# 780-00057_rev1_Pg1_SCH_NRES_Crate_Slot_M.net
KiCad netlist of a schematic drawn in Altium Designer
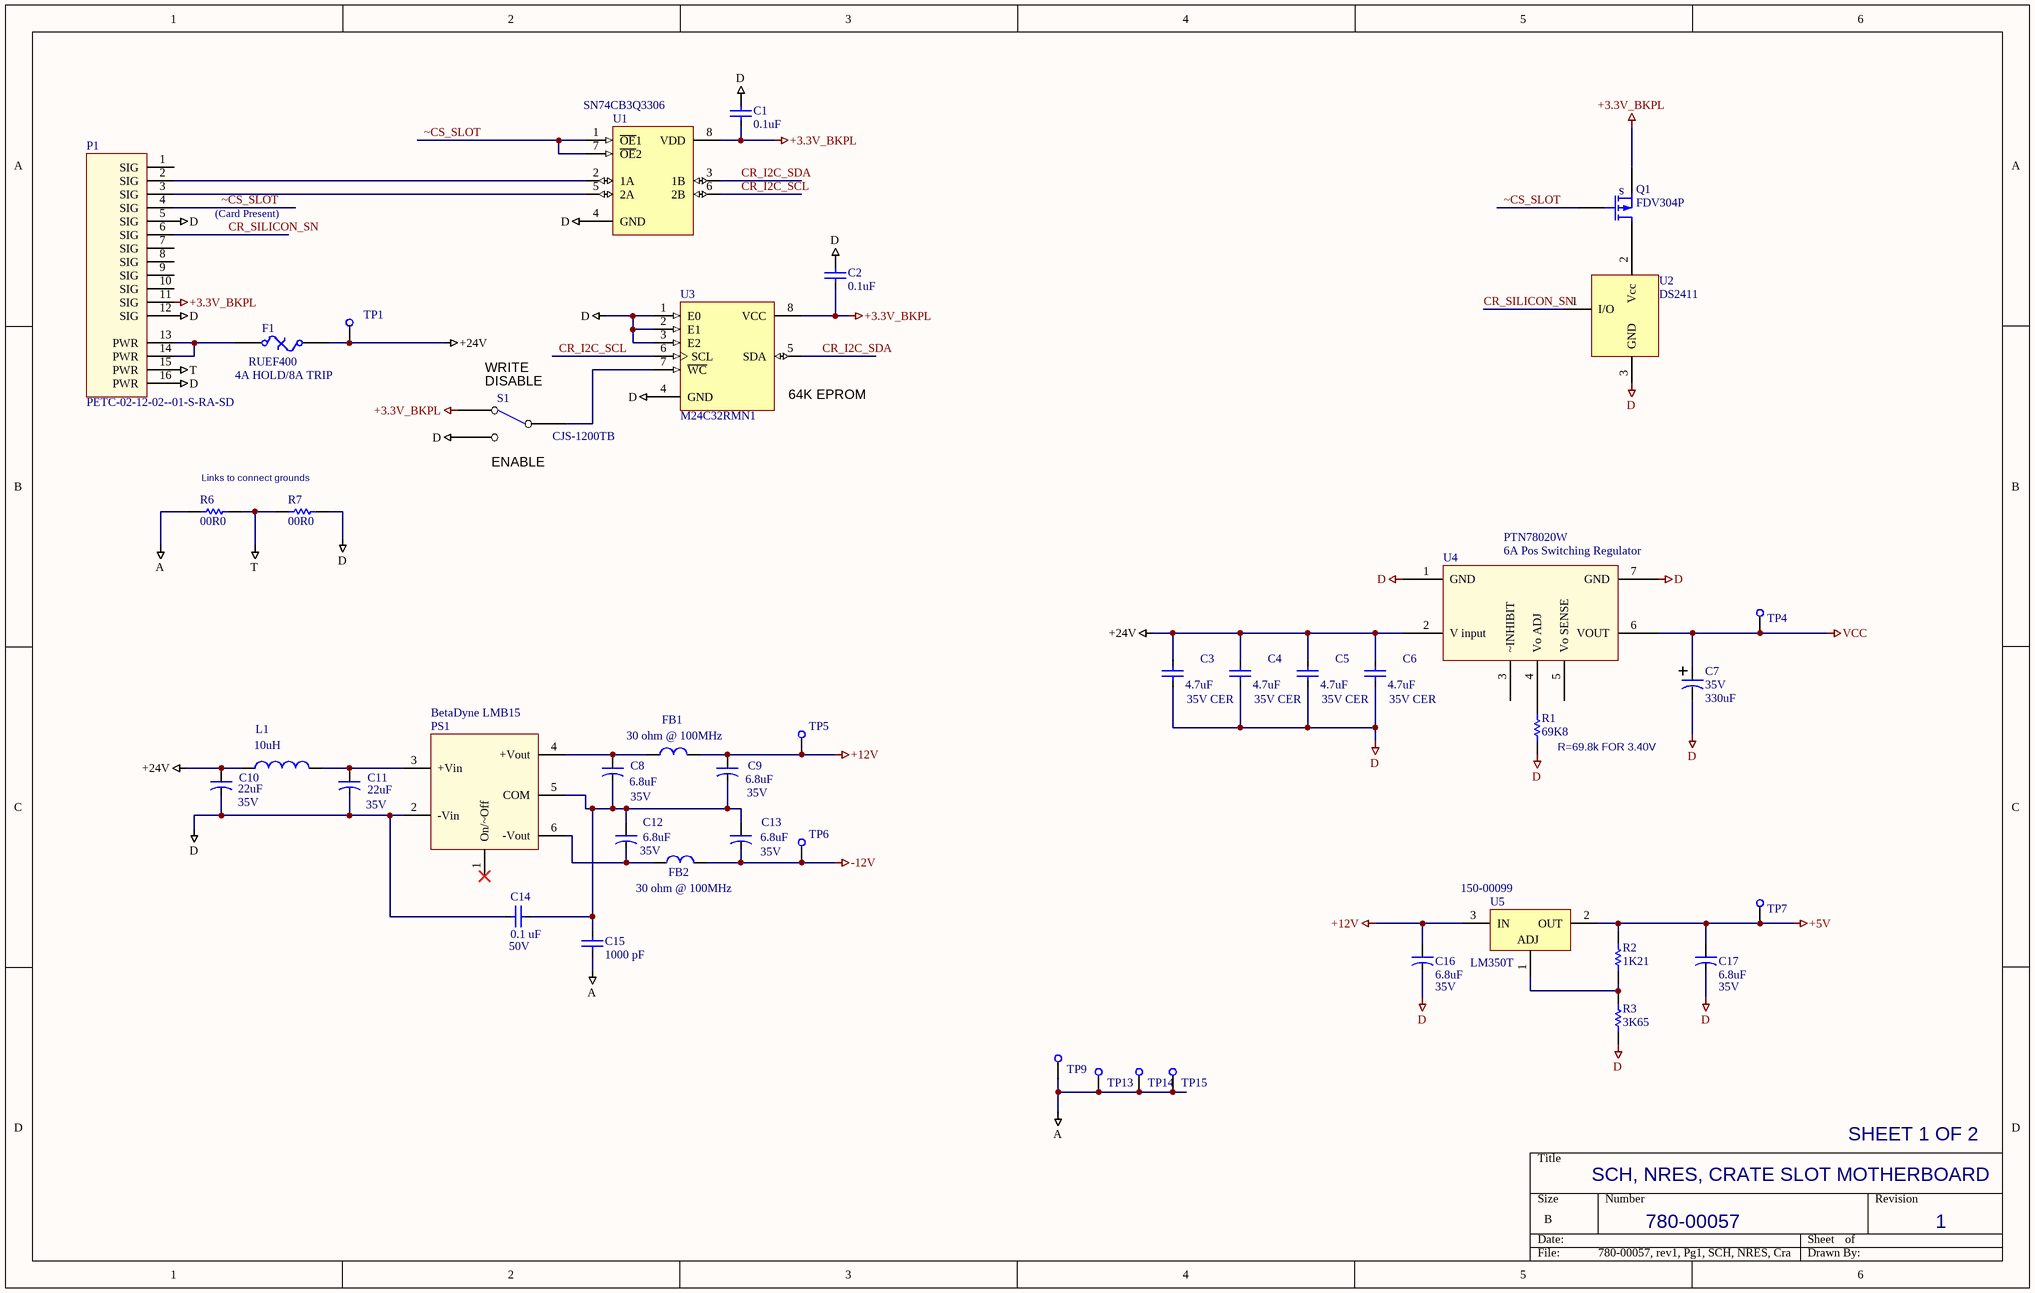
[diagram p0: 780-00057, rev1, Pg1, SCH, NRES, Crate Slot MotherBoard.SchDoc]

(export (version "E")
  (design (tool "Eeschema 10.0.6"))
  (components
    (comp (ref "C1")
      (value "0.1uF")
      (footprint "SMD_0805")
      (description "Capacitor")
      (fields (field (name "MANUFACTURER") "AVX") (field (name "Comment") "Cap SMD"))
      (libsource (lib "Richs Schematic Components") (part "Cap SMD"))
    )
    (comp (ref "C2")
      (value "0.1uF")
      (footprint "SMD_0805")
      (description "Capacitor")
      (fields (field (name "MANUFACTURER") "AVX") (field (name "Comment") "Cap SMD"))
      (libsource (lib "Richs Schematic Components") (part "Cap SMD"))
    )
    (comp (ref "C3")
      (value "35V CER")
      (footprint "SMD_0805")
      (description "Capacitor")
      (fields (field (name "ALTIUM_VALUE") "4.7uF"))
      (libsource (lib "Richs Schematic Components") (part "Cap SMD"))
    )
    (comp (ref "C4")
      (value "35V CER")
      (footprint "SMD_0805")
      (description "Capacitor")
      (fields (field (name "ALTIUM_VALUE") "4.7uF"))
      (libsource (lib "Richs Schematic Components") (part "Cap SMD"))
    )
    (comp (ref "C5")
      (value "35V CER")
      (footprint "SMD_0805")
      (description "Capacitor")
      (fields (field (name "ALTIUM_VALUE") "4.7uF"))
      (libsource (lib "Richs Schematic Components") (part "Cap SMD"))
    )
    (comp (ref "C6")
      (value "35V CER")
      (footprint "SMD_0805")
      (description "Capacitor")
      (fields (field (name "ALTIUM_VALUE") "4.7uF"))
      (libsource (lib "Richs Schematic Components") (part "Cap SMD"))
    )
    (comp (ref "C7")
      (value "35V")
      (footprint "CAP, Thru Hole 10mm dia")
      (description "Radial Thru hole")
      (fields (field (name "ALTIUM_VALUE") "330uF"))
      (libsource (lib "Richs Schematic Components") (part "Cap Elec, 330 uF, 35V"))
    )
    (comp (ref "C8")
      (value "35V")
      (footprint "SMD_CAP_6032")
      (description "outline 6.0mm x 3.2mm")
      (fields (field (name "ALTIUM_VALUE") "6.8uF"))
      (libsource (lib "Richs Schematic Components") (part "Cap Tant 35V"))
    )
    (comp (ref "C9")
      (value "35V")
      (footprint "SMD_CAP_6032")
      (description "outline 6.0mm x 3.2mm")
      (fields (field (name "ALTIUM_VALUE") "6.8uF"))
      (libsource (lib "Richs Schematic Components") (part "Cap Tant 35V"))
    )
    (comp (ref "C10")
      (value "35V")
      (footprint "SMD_CAP_7343")
      (description "outline 6.0mm x 3.2mm")
      (fields (field (name "MANUFACTURER") "Kemet") (field (name "ALTIUM_VALUE") "22uF"))
      (libsource (lib "Richs Schematic Components") (part "Cap Tant 35V"))
    )
    (comp (ref "C11")
      (value "35V")
      (footprint "SMD_CAP_7343")
      (description "outline 6.0mm x 3.2mm")
      (fields (field (name "MANUFACTURER") "Kemet") (field (name "ALTIUM_VALUE") "22uF"))
      (libsource (lib "Richs Schematic Components") (part "Cap Tant 35V"))
    )
    (comp (ref "C12")
      (value "35V")
      (footprint "SMD_CAP_6032")
      (description "outline 6.0mm x 3.2mm")
      (fields (field (name "ALTIUM_VALUE") "6.8uF"))
      (libsource (lib "Richs Schematic Components") (part "Cap Tant 35V"))
    )
    (comp (ref "C13")
      (value "35V")
      (footprint "SMD_CAP_6032")
      (description "outline 6.0mm x 3.2mm")
      (fields (field (name "ALTIUM_VALUE") "6.8uF"))
      (libsource (lib "Richs Schematic Components") (part "Cap Tant 35V"))
    )
    (comp (ref "C14")
      (value "50V")
      (footprint "SMD_0805")
      (description "Capacitor")
      (fields (field (name "ALTIUM_VALUE") "0.1 uF"))
      (libsource (lib "Richs Schematic Components") (part "Cap SMD"))
    )
    (comp (ref "C15")
      (value "1000 pF")
      (footprint "SMD_0805")
      (description "Capacitor")
      (fields (field (name "Comment") "Cap SMD"))
      (libsource (lib "Richs Schematic Components") (part "Cap SMD"))
    )
    (comp (ref "C16")
      (value "35V")
      (footprint "SMD_CAP_6032")
      (description "outline 6.0mm x 3.2mm")
      (fields (field (name "ALTIUM_VALUE") "6.8uF") (field (name "MANUFACTURER") "NICHICON"))
      (libsource (lib "Richs Schematic Components") (part "Cap Tant 35V"))
    )
    (comp (ref "C17")
      (value "35V")
      (footprint "SMD_CAP_6032")
      (description "outline 6.0mm x 3.2mm")
      (fields (field (name "ALTIUM_VALUE") "6.8uF") (field (name "MANUFACTURER") "NICHICON"))
      (libsource (lib "Richs Schematic Components") (part "Cap Tant 35V"))
    )
    (comp (ref "F1")
      (value "RUEF400")
      (footprint "PolySwitch Radial 0.2")
      (description "PolySwitch RUE Series")
      (fields
        (field (name "MANUFACTURER") "Tyco Electronics")
        (field (name "ALTIUM_VALUE") "4A HOLD/8A TRIP")
      )
      (libsource (lib "Richs Schematic Components") (part "Fuse Thermal"))
    )
    (comp (ref "FB1")
      (value "30 ohm @ 100MHz")
      (footprint "SMD_1210_INDUCT")
      (description "Ferrite Bead  SMD 1210")
      (fields (field (name "MANUFACTURER") "Wurth") (field (name "Comment") "Bead"))
      (libsource (lib "Richs Schematic Components") (part "Ferrite Bead SMD 1210"))
    )
    (comp (ref "FB2")
      (value "30 ohm @ 100MHz")
      (footprint "SMD_1210_INDUCT")
      (description "Ferrite Bead  SMD 1210")
      (fields (field (name "MANUFACTURER") "Wurth") (field (name "Comment") "Bead"))
      (libsource (lib "Richs Schematic Components") (part "Ferrite Bead SMD 1210"))
    )
    (comp (ref "L1")
      (value "10uH")
      (footprint "Inductor TDC SLF")
      (description "Inductor")
      (fields (field (name "MANUFACTURER") "TDK") (field (name "Comment") "445-3869-1-ND"))
      (libsource (lib "Richs Schematic Components") (part "Inductor SMD 10uH 1.8A"))
    )
    (comp (ref "P1")
      (value "PETC-02-12-02--01-S-RA-SD")
      (footprint "PETC-02-12-02-01-RA")
      (description "SAMTEC, SIGNAL(12)+PWR(4)")
      (fields (field (name "MANUFACTURER") "SAMTEC"))
      (libsource (lib "Richs Schematic Components") (part "PETC-02-12-02--01-S-RA-SD"))
    )
    (comp (ref "PS1")
      (value "BetaDyne LMB15")
      (footprint "BetaDyne LNB15, DC/DC")
      (description "DC/DC LMB15 15W, Dual Output")
      (libsource (lib "Richs Schematic Components") (part "BetaDyne LMB15"))
    )
    (comp (ref "Q1")
      (value "FDV304P")
      (footprint "SMD_SOT23_3")
      (description "P-MOSFET LOGIC LEVEL")
      (fields (field (name "MANUFACTURER") "Fairchild"))
      (libsource (lib "Richs Schematic Components") (part "FDV304P"))
    )
    (comp (ref "R1")
      (value "69K8")
      (footprint "SMD_0805")
      (description "Resistor 0805")
      (fields (field (name "MANUFACTURER") "Vishay/Dale") (field (name "Comment") "Res 0805"))
      (libsource (lib "Richs Schematic Components") (part "Res SMD"))
    )
    (comp (ref "R2")
      (value "1K21")
      (footprint "SMD_0805")
      (description "Resistor 0805")
      (fields (field (name "MANUFACTURER") "Vishay/Dale") (field (name "Comment") "Res 0805"))
      (libsource (lib "Richs Schematic Components") (part "Res SMD"))
    )
    (comp (ref "R3")
      (value "3K65")
      (footprint "SMD_0805")
      (description "Resistor 0805")
      (fields (field (name "MANUFACTURER") "Vishay/Dale") (field (name "Comment") "Res 0805"))
      (libsource (lib "Richs Schematic Components") (part "Res SMD"))
    )
    (comp (ref "R6")
      (value "00R0")
      (footprint "Protel 99SE BANKS PCB:smd_0805")
      (description "Resistor 0805")
      (fields (field (name "MANUFACTURER") "Vishay/Dale") (field (name "Comment") "Res 0805"))
      (libsource (lib "Richs Schematic Components") (part "Res SMD"))
    )
    (comp (ref "R7")
      (value "00R0")
      (footprint "Protel 99SE BANKS PCB:smd_0805")
      (description "Resistor 0805")
      (fields (field (name "MANUFACTURER") "Vishay/Dale") (field (name "Comment") "Res 0805"))
      (libsource (lib "Richs Schematic Components") (part "Res SMD"))
    )
    (comp (ref "S1")
      (value "CJS-1200TB")
      (footprint "CAS-120B")
      (fields (field (name "MANUFACTURER") "Copal Electronics"))
      (libsource (lib "JON_1_Library") (part "SW_SPDT_DOUG"))
    )
    (comp (ref "TP1")
      (value "Test point")
      (footprint "Protel 99SE BANKS PCB:PAD_80D_052H")
      (description "Test Point")
      (fields (field (name "MANUFACTURER") "Keystone"))
      (libsource (lib "Richs Schematic Components") (part "Test point"))
    )
    (comp (ref "TP4")
      (value "Test point")
      (footprint "Protel 99SE BANKS PCB:PAD_80D_052H")
      (description "Test Point")
      (fields (field (name "MANUFACTURER") "Keystone"))
      (libsource (lib "Richs Schematic Components") (part "Test point"))
    )
    (comp (ref "TP5")
      (value "Test point")
      (footprint "Protel 99SE BANKS PCB:PAD_80D_052H")
      (description "Test Point")
      (fields (field (name "MANUFACTURER") "Keystone"))
      (libsource (lib "Richs Schematic Components") (part "Test point"))
    )
    (comp (ref "TP6")
      (value "Test point")
      (footprint "Protel 99SE BANKS PCB:PAD_80D_052H")
      (description "Test Point")
      (fields (field (name "MANUFACTURER") "Keystone"))
      (libsource (lib "Richs Schematic Components") (part "Test point"))
    )
    (comp (ref "TP7")
      (value "Test point")
      (footprint "Protel 99SE BANKS PCB:PAD_80D_052H")
      (description "Test Point")
      (fields (field (name "MANUFACTURER") "Keystone"))
      (libsource (lib "Richs Schematic Components") (part "Test point"))
    )
    (comp (ref "TP9")
      (value "Test point")
      (footprint "Protel 99SE BANKS PCB:PAD_80D_052H")
      (description "Test Point")
      (fields (field (name "MANUFACTURER") "Keystone"))
      (libsource (lib "Richs Schematic Components") (part "Test point"))
    )
    (comp (ref "TP13")
      (value "Test point")
      (footprint "Protel 99SE BANKS PCB:PAD_80D_052H")
      (description "Test Point")
      (fields (field (name "MANUFACTURER") "Keystone"))
      (libsource (lib "Richs Schematic Components") (part "Test point"))
    )
    (comp (ref "TP14")
      (value "Test point")
      (footprint "Protel 99SE BANKS PCB:PAD_80D_052H")
      (description "Test Point")
      (fields (field (name "MANUFACTURER") "Keystone"))
      (libsource (lib "Richs Schematic Components") (part "Test point"))
    )
    (comp (ref "TP15")
      (value "Test point")
      (footprint "Protel 99SE BANKS PCB:PAD_80D_052H")
      (description "Test Point")
      (fields (field (name "MANUFACTURER") "Keystone"))
      (libsource (lib "Richs Schematic Components") (part "Test point"))
    )
    (comp (ref "U1")
      (value "SN74CB3Q3306")
      (footprint "PW008_N")
      (description "Dual FET Bus Switch")
      (fields (field (name "MANUFACTURER") "TI") (field (name "Comment") "SN74CBT3306PWLE"))
      (libsource (lib "TI Logic Switch") (part "SN74CBT3306PWLE"))
    )
    (comp (ref "U2")
      (value "DS2411")
      (footprint "SMD_SOT23_3")
      (description "Silicon Serial Number")
      (fields (field (name "MANUFACTURER") "MAXIM"))
      (libsource (lib "Richs Schematic Components") (part "DS2411"))
    )
    (comp (ref "U3")
      (value "M24C32RMN1")
      (footprint "SOP8_N")
      (description "32 Kbit Serial I²C Bus EEPROM")
      (libsource (lib "ST Memory EEPROM Serial") (part "M24C32RMN1"))
    )
    (comp (ref "U4")
      (value "6A Pos Switching Regulator")
      (footprint "TEXAS Inst Switching Regulator")
      (description "Pos Adj Switching Regulator")
      (fields (field (name "ALTIUM_VALUE") "PTN78020W"))
      (libsource (lib "Richs Schematic Components") (part "PTN78020W"))
    )
    (comp (ref "U5")
      (value "LM350T")
      (footprint "TO-220AB")
      (description "3-Amp Adjustable Regulator")
      (fields (field (name "MANUFACTURER") "National Semiconductor") (field (name "LCO P/N") "150-00099"))
      (libsource (lib "NSC LDO") (part "LM350T"))
    )
  )
  (nets
    (net (code "1") (name "+3.3V_BKPL") (class "Default")
      (node (ref "C1") (pin "1") (pinfunction "1_1") (pintype "passive"))
      (node (ref "C2") (pin "1") (pinfunction "1_1") (pintype "passive"))
      (node (ref "P1") (pin "11") (pinfunction "SIG_11") (pintype "passive"))
      (node (ref "Q1") (pin "2") (pinfunction "S_2") (pintype "passive"))
      (node (ref "S1") (pin "3") (pinfunction "NC_3") (pintype "passive"))
      (node (ref "U1") (pin "8") (pinfunction "VDD_8") (pintype "power_in"))
      (node (ref "U3") (pin "8") (pinfunction "VCC_8") (pintype "power_in"))
    )
    (net (code "2") (name "+5V") (class "Default")
      (node (ref "C17") (pin "pos") (pinfunction "1_pos") (pintype "passive"))
      (node (ref "R2") (pin "2") (pinfunction "2_2") (pintype "passive"))
      (node (ref "TP7") (pin "1") (pinfunction "TP_1") (pintype "passive"))
      (node (ref "U5") (pin "2") (pinfunction "OUT_2") (pintype "power_in"))
    )
    (net (code "3") (name "+12V") (class "Default")
      (node (ref "C16") (pin "pos") (pinfunction "1_pos") (pintype "passive"))
      (node (ref "C9") (pin "pos") (pinfunction "1_pos") (pintype "passive"))
      (node (ref "FB1") (pin "2") (pinfunction "2_2") (pintype "passive"))
      (node (ref "TP5") (pin "1") (pinfunction "TP_1") (pintype "passive"))
      (node (ref "U5") (pin "3") (pinfunction "IN_3") (pintype "passive"))
    )
    (net (code "4") (name "+24V") (class "Default")
      (node (ref "C10") (pin "pos") (pinfunction "1_pos") (pintype "passive"))
      (node (ref "C3") (pin "2") (pinfunction "2_2") (pintype "passive"))
      (node (ref "C4") (pin "2") (pinfunction "2_2") (pintype "passive"))
      (node (ref "C5") (pin "2") (pinfunction "2_2") (pintype "passive"))
      (node (ref "C6") (pin "2") (pinfunction "2_2") (pintype "passive"))
      (node (ref "F1") (pin "2") (pinfunction "2_2") (pintype "passive"))
      (node (ref "L1") (pin "1") (pinfunction "1_1") (pintype "passive"))
      (node (ref "TP1") (pin "1") (pinfunction "TP_1") (pintype "passive"))
      (node (ref "U4") (pin "2") (pinfunction "V_input_2") (pintype "passive"))
    )
    (net (code "5") (name "-12V") (class "Default")
      (node (ref "C13") (pin "neg") (pinfunction "2_neg") (pintype "passive"))
      (node (ref "FB2") (pin "2") (pinfunction "2_2") (pintype "passive"))
      (node (ref "TP6") (pin "1") (pinfunction "TP_1") (pintype "passive"))
    )
    (net (code "6") (name "/CR_I2C_SCL") (class "Default")
      (node (ref "U1") (pin "6") (pinfunction "2B_6") (pintype "bidirectional"))
      (node (ref "U3") (pin "6") (pinfunction "SCL_6") (pintype "input"))
    )
    (net (code "7") (name "/CR_I2C_SDA") (class "Default")
      (node (ref "U1") (pin "3") (pinfunction "1B_3") (pintype "bidirectional"))
      (node (ref "U3") (pin "5") (pinfunction "SDA_5") (pintype "bidirectional"))
    )
    (net (code "8") (name "/CR_SILICON_SN") (class "Default")
      (node (ref "P1") (pin "6") (pinfunction "SIG_6") (pintype "passive"))
      (node (ref "U2") (pin "1") (pinfunction "I/O_1") (pintype "passive"))
    )
    (net (code "9") (name "/~CS_SLOT") (class "Default")
      (node (ref "P1") (pin "4") (pinfunction "SIG_4") (pintype "passive"))
      (node (ref "Q1") (pin "1") (pinfunction "G_1") (pintype "passive"))
      (node (ref "U1") (pin "1") (pinfunction "~{OE}1_1") (pintype "input"))
      (node (ref "U1") (pin "7") (pinfunction "~{OE}2_7") (pintype "input"))
    )
    (net (code "10") (name "A") (class "Default")
      (node (ref "C15") (pin "1") (pinfunction "1_1") (pintype "passive"))
      (node (ref "R6") (pin "1") (pinfunction "1_1") (pintype "passive"))
      (node (ref "TP13") (pin "1") (pinfunction "TP_1") (pintype "passive"))
      (node (ref "TP14") (pin "1") (pinfunction "TP_1") (pintype "passive"))
      (node (ref "TP15") (pin "1") (pinfunction "TP_1") (pintype "passive"))
      (node (ref "TP9") (pin "1") (pinfunction "TP_1") (pintype "passive"))
    )
    (net (code "11") (name "D") (class "Default")
      (node (ref "C1") (pin "2") (pinfunction "2_2") (pintype "passive"))
      (node (ref "C10") (pin "neg") (pinfunction "2_neg") (pintype "passive"))
      (node (ref "C11") (pin "neg") (pinfunction "2_neg") (pintype "passive"))
      (node (ref "C14") (pin "1") (pinfunction "1_1") (pintype "passive"))
      (node (ref "C16") (pin "neg") (pinfunction "2_neg") (pintype "passive"))
      (node (ref "C17") (pin "neg") (pinfunction "2_neg") (pintype "passive"))
      (node (ref "C2") (pin "2") (pinfunction "2_2") (pintype "passive"))
      (node (ref "C3") (pin "1") (pinfunction "1_1") (pintype "passive"))
      (node (ref "C4") (pin "1") (pinfunction "1_1") (pintype "passive"))
      (node (ref "C5") (pin "1") (pinfunction "1_1") (pintype "passive"))
      (node (ref "C6") (pin "1") (pinfunction "1_1") (pintype "passive"))
      (node (ref "C7") (pin "2") (pinfunction "2_2") (pintype "passive"))
      (node (ref "P1") (pin "12") (pinfunction "SIG_12") (pintype "passive"))
      (node (ref "P1") (pin "16") (pinfunction "PWR_16") (pintype "passive"))
      (node (ref "P1") (pin "5") (pinfunction "SIG_5") (pintype "passive"))
      (node (ref "PS1") (pin "2") (pinfunction "-Vin_2") (pintype "passive"))
      (node (ref "R1") (pin "1") (pinfunction "1_1") (pintype "passive"))
      (node (ref "R3") (pin "1") (pinfunction "1_1") (pintype "passive"))
      (node (ref "R7") (pin "2") (pinfunction "2_2") (pintype "passive"))
      (node (ref "S1") (pin "1") (pinfunction "NO_1") (pintype "passive"))
      (node (ref "U1") (pin "4") (pinfunction "GND_4") (pintype "power_in"))
      (node (ref "U2") (pin "3") (pinfunction "GND_3") (pintype "passive"))
      (node (ref "U3") (pin "1") (pinfunction "E0_1") (pintype "input"))
      (node (ref "U3") (pin "2") (pinfunction "E1_2") (pintype "input"))
      (node (ref "U3") (pin "3") (pinfunction "E2_3") (pintype "input"))
      (node (ref "U3") (pin "4") (pinfunction "GND_4") (pintype "power_in"))
      (node (ref "U4") (pin "1") (pinfunction "GND_1") (pintype "passive"))
      (node (ref "U4") (pin "7") (pinfunction "GND_7") (pintype "passive"))
    )
    (net (code "12") (name "Net-(C8-1)") (class "Default")
      (node (ref "C8") (pin "pos") (pinfunction "1_pos") (pintype "passive"))
      (node (ref "FB1") (pin "1") (pinfunction "1_1") (pintype "passive"))
      (node (ref "PS1") (pin "4") (pinfunction "+Vout_4") (pintype "passive"))
    )
    (net (code "13") (name "Net-(C11-1)") (class "Default")
      (node (ref "C11") (pin "pos") (pinfunction "1_pos") (pintype "passive"))
      (node (ref "L1") (pin "2") (pinfunction "2_2") (pintype "passive"))
      (node (ref "PS1") (pin "3") (pinfunction "+Vin_3") (pintype "passive"))
    )
    (net (code "14") (name "Net-(C12-1)") (class "Default")
      (node (ref "C12") (pin "pos") (pinfunction "1_pos") (pintype "passive"))
      (node (ref "C13") (pin "pos") (pinfunction "1_pos") (pintype "passive"))
      (node (ref "C14") (pin "2") (pinfunction "2_2") (pintype "passive"))
      (node (ref "C15") (pin "2") (pinfunction "2_2") (pintype "passive"))
      (node (ref "C8") (pin "neg") (pinfunction "2_neg") (pintype "passive"))
      (node (ref "C9") (pin "neg") (pinfunction "2_neg") (pintype "passive"))
      (node (ref "PS1") (pin "5") (pinfunction "COM_5") (pintype "passive"))
    )
    (net (code "15") (name "Net-(C12-2)") (class "Default")
      (node (ref "C12") (pin "neg") (pinfunction "2_neg") (pintype "passive"))
      (node (ref "FB2") (pin "1") (pinfunction "1_1") (pintype "passive"))
      (node (ref "PS1") (pin "6") (pinfunction "-Vout_6") (pintype "passive"))
    )
    (net (code "16") (name "Net-(F1-Pad1)") (class "Default")
      (node (ref "F1") (pin "1") (pinfunction "1_1") (pintype "passive"))
      (node (ref "P1") (pin "13") (pinfunction "PWR_13") (pintype "passive"))
      (node (ref "P1") (pin "14") (pinfunction "PWR_14") (pintype "passive"))
    )
    (net (code "17") (name "Net-(Q1-D)") (class "Default")
      (node (ref "Q1") (pin "3") (pinfunction "D_3") (pintype "passive"))
      (node (ref "U2") (pin "2") (pinfunction "Vcc_2") (pintype "passive"))
    )
    (net (code "18") (name "Net-(S1-COM)") (class "Default")
      (node (ref "S1") (pin "2") (pinfunction "COM_2") (pintype "passive"))
      (node (ref "U3") (pin "7") (pinfunction "~{WC}_7") (pintype "input"))
    )
    (net (code "19") (name "Net-(U1-1A)") (class "Default")
      (node (ref "P1") (pin "2") (pinfunction "SIG_2") (pintype "passive"))
      (node (ref "U1") (pin "2") (pinfunction "1A_2") (pintype "bidirectional"))
    )
    (net (code "20") (name "Net-(U1-2A)") (class "Default")
      (node (ref "P1") (pin "3") (pinfunction "SIG_3") (pintype "passive"))
      (node (ref "U1") (pin "5") (pinfunction "2A_5") (pintype "bidirectional"))
    )
    (net (code "21") (name "Net-(U4-Vo_ADJ)") (class "Default")
      (node (ref "R1") (pin "2") (pinfunction "2_2") (pintype "passive"))
      (node (ref "U4") (pin "4") (pinfunction "Vo_ADJ_4") (pintype "passive"))
    )
    (net (code "22") (name "Net-(U5-ADJ)") (class "Default")
      (node (ref "R2") (pin "1") (pinfunction "1_1") (pintype "passive"))
      (node (ref "R3") (pin "2") (pinfunction "2_2") (pintype "passive"))
      (node (ref "U5") (pin "1") (pinfunction "ADJ_1") (pintype "power_in"))
    )
    (net (code "23") (name "T") (class "Default")
      (node (ref "P1") (pin "15") (pinfunction "PWR_15") (pintype "passive"))
      (node (ref "R6") (pin "2") (pinfunction "2_2") (pintype "passive"))
      (node (ref "R7") (pin "1") (pinfunction "1_1") (pintype "passive"))
    )
    (net (code "24") (name "VCC") (class "Default")
      (node (ref "C7") (pin "1") (pinfunction "1_1") (pintype "passive"))
      (node (ref "TP4") (pin "1") (pinfunction "TP_1") (pintype "passive"))
      (node (ref "U4") (pin "6") (pinfunction "VOUT_6") (pintype "passive"))
    )
    (net (code "25") (name "unconnected-(P1-SIG-Pad1)") (class "Default")
      (node (ref "P1") (pin "1") (pinfunction "SIG_1") (pintype "passive"))
    )
    (net (code "26") (name "unconnected-(P1-SIG-Pad7)") (class "Default")
      (node (ref "P1") (pin "7") (pinfunction "SIG_7") (pintype "passive"))
    )
    (net (code "27") (name "unconnected-(P1-SIG-Pad8)") (class "Default")
      (node (ref "P1") (pin "8") (pinfunction "SIG_8") (pintype "passive"))
    )
    (net (code "28") (name "unconnected-(P1-SIG-Pad9)") (class "Default")
      (node (ref "P1") (pin "9") (pinfunction "SIG_9") (pintype "passive"))
    )
    (net (code "29") (name "unconnected-(P1-SIG-Pad10)") (class "Default")
      (node (ref "P1") (pin "10") (pinfunction "SIG_10") (pintype "passive"))
    )
    (net (code "30") (name "unconnected-(PS1-On{slash}~Off-Pad1)") (class "Default")
      (node (ref "PS1") (pin "1") (pinfunction "On/~Off_1") (pintype "passive+no_connect"))
    )
    (net (code "31") (name "unconnected-(U4-Vo_SENSE-Pad5)") (class "Default")
      (node (ref "U4") (pin "5") (pinfunction "Vo_SENSE_5") (pintype "passive"))
    )
    (net (code "32") (name "unconnected-(U4-~INHIBIT-Pad3)") (class "Default")
      (node (ref "U4") (pin "3") (pinfunction "~INHIBIT_3") (pintype "passive"))
    )
  )
)
